# MCU063B_EtherCAT.net
KiCad netlist of a schematic drawn in Altium Designer
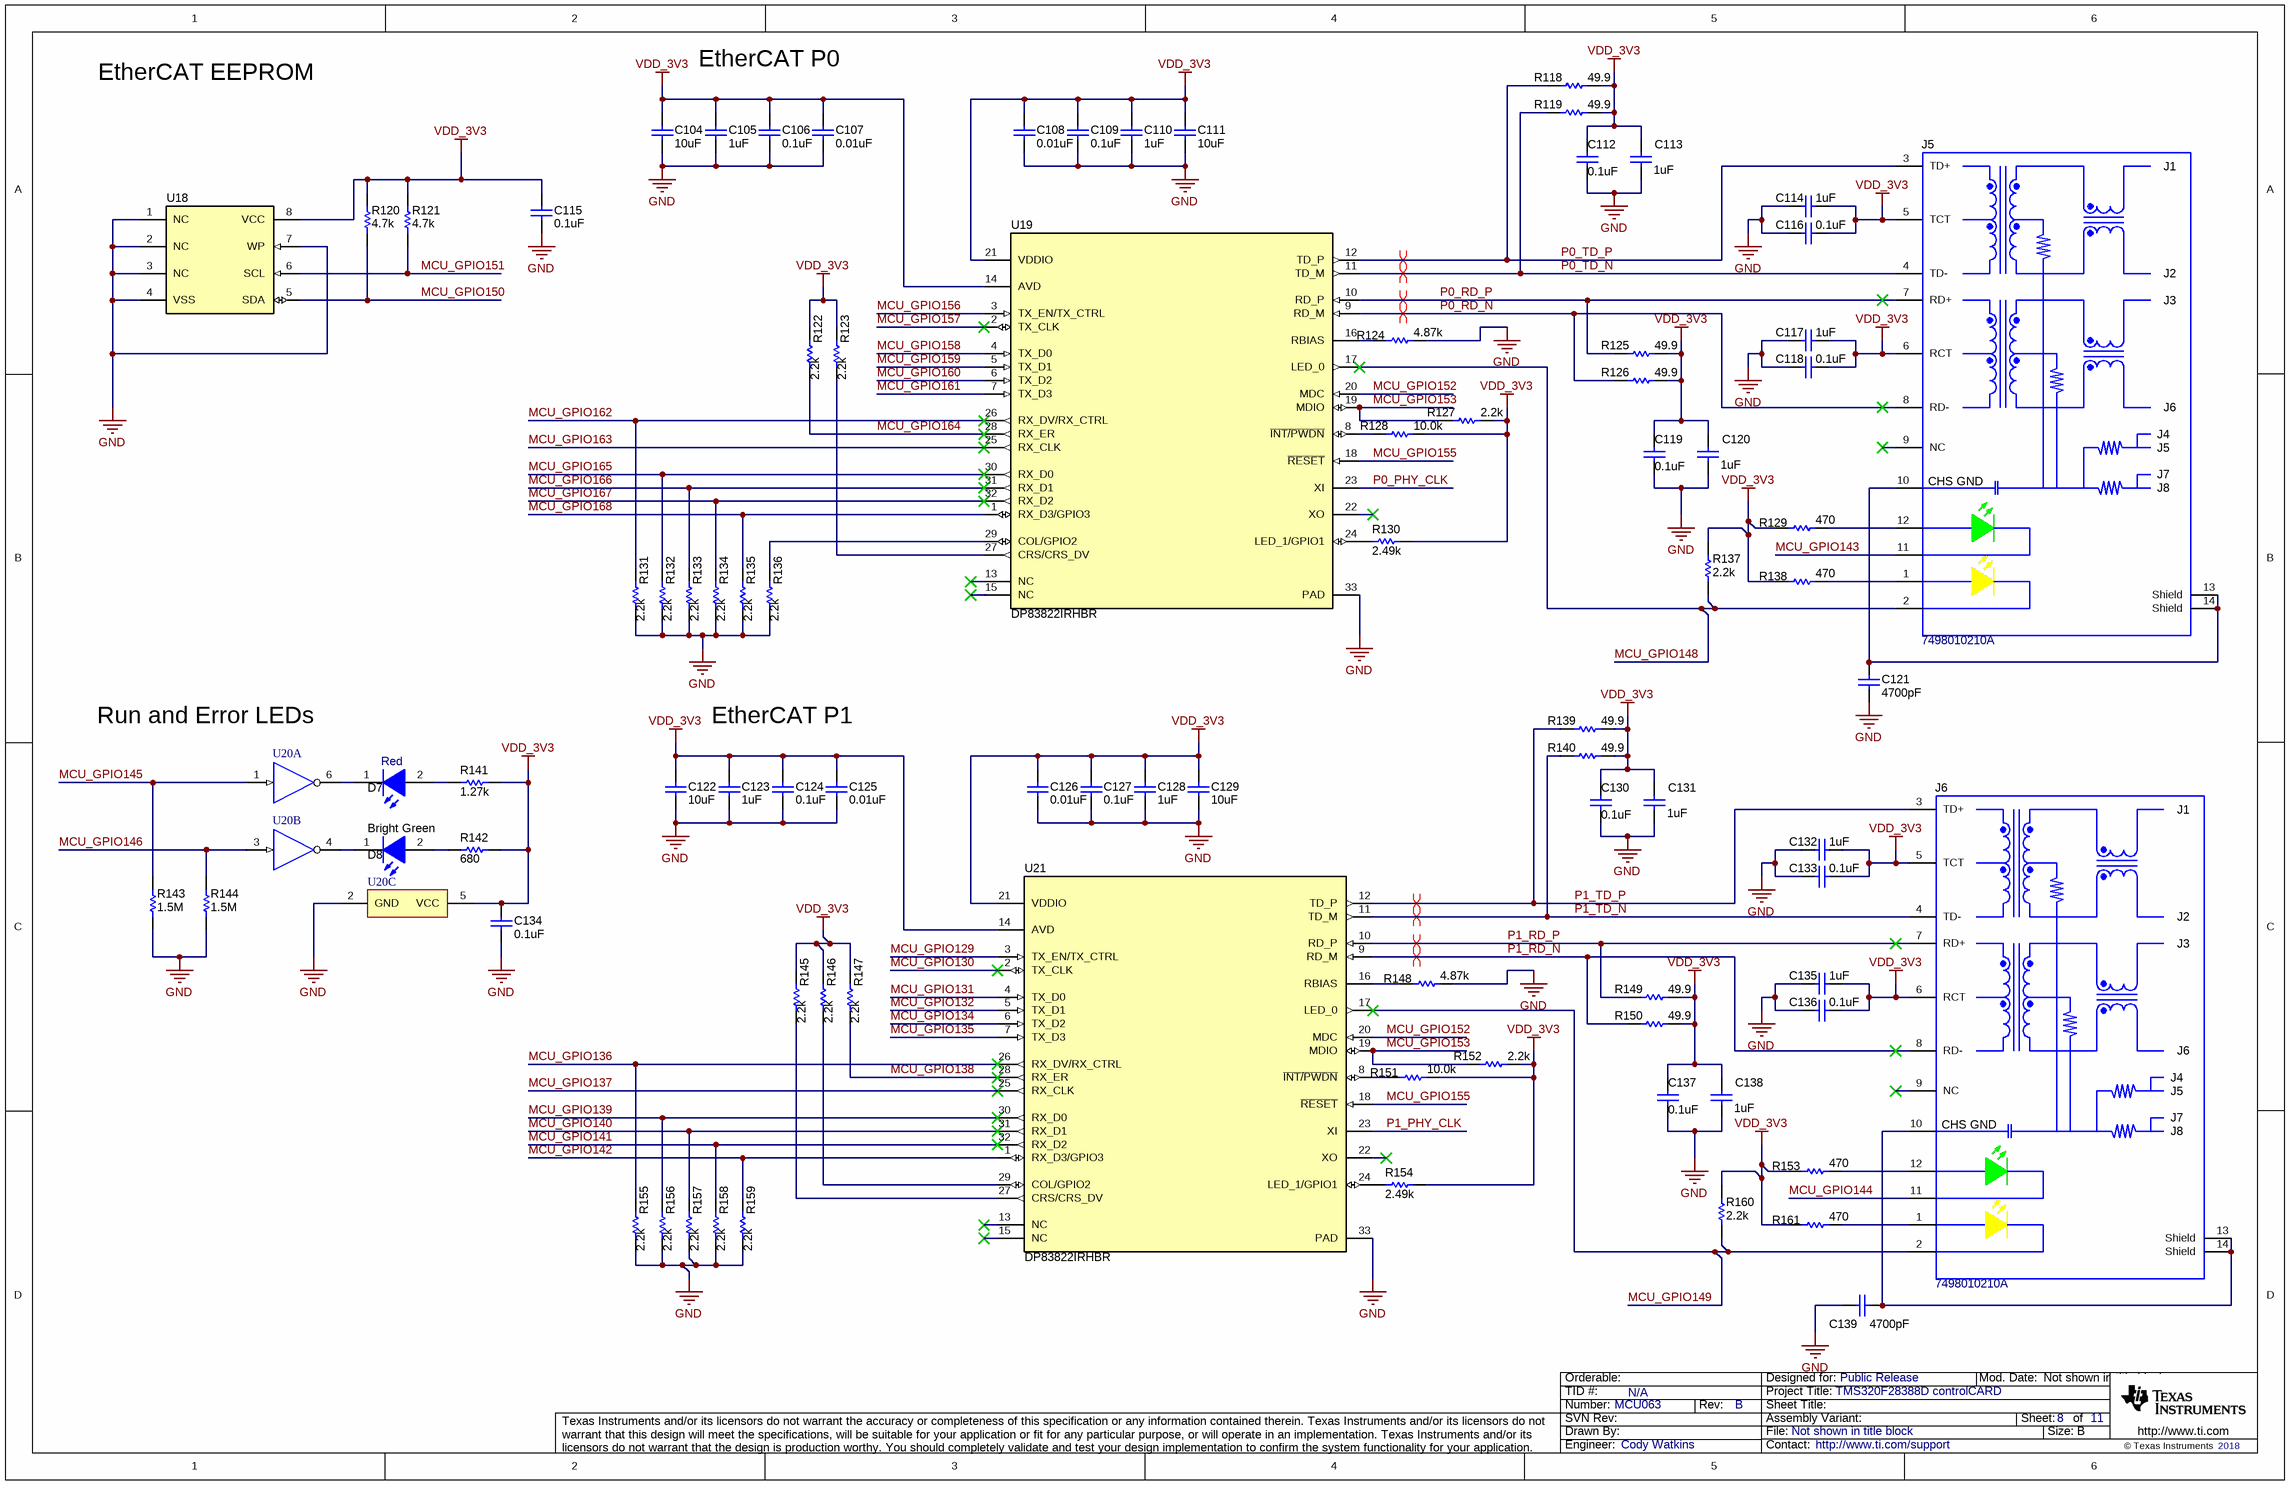
[diagram p0: MCU063B_EtherCAT.SchDoc]

(export (version "E")
  (design (tool "Eeschema 10.0.6"))
  (components
    (comp (ref "C104")
      (value "CL05A106MQ5NUNC")
      (footprint "0402")
      (description "CAP, CERM, 10 uF, 6.3 V, +/- 20%, X5R, 0402")
      (fields
        (field (name "MANUFACTURER") "Samsung Electro-Mechanics")
        (field (name "VALUEDISPLAYED") "10uF")
      )
      (libsource (lib "Altium Vault - TI") (part "Capacitor"))
    )
    (comp (ref "C105")
      (value "EMK105BJ105KVHF")
      (footprint "0402")
      (description "CAP, CERM, 1 uF, 16 V, +/- 10%, X5R, 0402")
      (fields (field (name "MANUFACTURER") "Taiyo Yuden") (field (name "VALUEDISPLAYED") "1uF"))
      (libsource (lib "Altium Vault - TI") (part "Capacitor"))
    )
    (comp (ref "C106")
      (value "LMK105BJ104KV-F")
      (footprint "0402")
      (description "CAP, CERM, 0.1 uF, 10 V,+/- 10%, X5R, 0402")
      (fields (field (name "MANUFACTURER") "Taiyo Yuden") (field (name "VALUEDISPLAYED") "0.1uF"))
      (libsource (lib "Altium Vault - TI") (part "Capacitor"))
    )
    (comp (ref "C107")
      (value "885012205031")
      (footprint "0402")
      (description "CAP, CERM, 0.01 uF, 16 V, +/- 10%, X7R, 0402")
      (fields (field (name "MANUFACTURER") "Wurth Elektronik") (field (name "VALUEDISPLAYED") "0.01uF"))
      (libsource (lib "Altium Vault - TI") (part "Capacitor"))
    )
    (comp (ref "C108")
      (value "885012205031")
      (footprint "0402")
      (description "CAP, CERM, 0.01 uF, 16 V, +/- 10%, X7R, 0402")
      (fields (field (name "MANUFACTURER") "Wurth Elektronik") (field (name "VALUEDISPLAYED") "0.01uF"))
      (libsource (lib "Altium Vault - TI") (part "Capacitor"))
    )
    (comp (ref "C109")
      (value "LMK105BJ104KV-F")
      (footprint "0402")
      (description "CAP, CERM, 0.1 uF, 10 V,+/- 10%, X5R, 0402")
      (fields (field (name "MANUFACTURER") "Taiyo Yuden") (field (name "VALUEDISPLAYED") "0.1uF"))
      (libsource (lib "Altium Vault - TI") (part "Capacitor"))
    )
    (comp (ref "C110")
      (value "EMK105BJ105KVHF")
      (footprint "0402")
      (description "CAP, CERM, 1 uF, 16 V, +/- 10%, X5R, 0402")
      (fields (field (name "MANUFACTURER") "Taiyo Yuden") (field (name "VALUEDISPLAYED") "1uF"))
      (libsource (lib "Altium Vault - TI") (part "Capacitor"))
    )
    (comp (ref "C111")
      (value "CL05A106MQ5NUNC")
      (footprint "0402")
      (description "CAP, CERM, 10 uF, 6.3 V, +/- 20%, X5R, 0402")
      (fields
        (field (name "MANUFACTURER") "Samsung Electro-Mechanics")
        (field (name "VALUEDISPLAYED") "10uF")
      )
      (libsource (lib "Altium Vault - TI") (part "Capacitor"))
    )
    (comp (ref "C112")
      (value "LMK105BJ104KV-F")
      (footprint "0402")
      (description "CAP, CERM, 0.1 uF, 10 V,+/- 10%, X5R, 0402")
      (fields (field (name "MANUFACTURER") "Taiyo Yuden") (field (name "VALUEDISPLAYED") "0.1uF"))
      (libsource (lib "Altium Vault - TI") (part "Capacitor"))
    )
    (comp (ref "C113")
      (value "EMK105BJ105KVHF")
      (footprint "0402")
      (description "CAP, CERM, 1 uF, 16 V, +/- 10%, X5R, 0402")
      (fields (field (name "MANUFACTURER") "Taiyo Yuden") (field (name "VALUEDISPLAYED") "1uF"))
      (libsource (lib "Altium Vault - TI") (part "Capacitor"))
    )
    (comp (ref "C114")
      (value "EMK105BJ105KVHF")
      (footprint "0402")
      (description "CAP, CERM, 1 uF, 16 V, +/- 10%, X5R, 0402")
      (fields (field (name "MANUFACTURER") "Taiyo Yuden") (field (name "VALUEDISPLAYED") "1uF"))
      (libsource (lib "Altium Vault - TI") (part "Capacitor"))
    )
    (comp (ref "C115")
      (value "CL05B104KP5NNNC")
      (footprint "0402")
      (description "CAP, CERM, 0.1 uF, 10 V, +/- 10%, X7R, 0402")
      (fields
        (field (name "VALUEDISPLAYED") "0.1uF")
        (field (name "MANUFACTURER") "Samsung Electro-Mechanics")
      )
      (libsource (lib "Altium Vault - TI") (part "Capacitor"))
    )
    (comp (ref "C116")
      (value "LMK105BJ104KV-F")
      (footprint "0402")
      (description "CAP, CERM, 0.1 uF, 10 V,+/- 10%, X5R, 0402")
      (fields (field (name "MANUFACTURER") "Taiyo Yuden") (field (name "VALUEDISPLAYED") "0.1uF"))
      (libsource (lib "Altium Vault - TI") (part "Capacitor"))
    )
    (comp (ref "C117")
      (value "EMK105BJ105KVHF")
      (footprint "0402")
      (description "CAP, CERM, 1 uF, 16 V, +/- 10%, X5R, 0402")
      (fields (field (name "MANUFACTURER") "Taiyo Yuden") (field (name "VALUEDISPLAYED") "1uF"))
      (libsource (lib "Altium Vault - TI") (part "Capacitor"))
    )
    (comp (ref "C118")
      (value "LMK105BJ104KV-F")
      (footprint "0402")
      (description "CAP, CERM, 0.1 uF, 10 V,+/- 10%, X5R, 0402")
      (fields (field (name "MANUFACTURER") "Taiyo Yuden") (field (name "VALUEDISPLAYED") "0.1uF"))
      (libsource (lib "Altium Vault - TI") (part "Capacitor"))
    )
    (comp (ref "C119")
      (value "LMK105BJ104KV-F")
      (footprint "0402")
      (description "CAP, CERM, 0.1 uF, 10 V,+/- 10%, X5R, 0402")
      (fields (field (name "MANUFACTURER") "Taiyo Yuden") (field (name "VALUEDISPLAYED") "0.1uF"))
      (libsource (lib "Altium Vault - TI") (part "Capacitor"))
    )
    (comp (ref "C120")
      (value "EMK105BJ105KVHF")
      (footprint "0402")
      (description "CAP, CERM, 1 uF, 16 V, +/- 10%, X5R, 0402")
      (fields (field (name "MANUFACTURER") "Taiyo Yuden") (field (name "VALUEDISPLAYED") "1uF"))
      (libsource (lib "Altium Vault - TI") (part "Capacitor"))
    )
    (comp (ref "C121")
      (value "12061C472KAT2A")
      (footprint "1206")
      (description "CAP, CERM, 4700 pF, 100 V, +/- 10%, X7R, 1206")
      (fields (field (name "MANUFACTURER") "AVX") (field (name "VALUEDISPLAYED") "4700pF"))
      (libsource (lib "Altium Vault - TI") (part "Capacitor"))
    )
    (comp (ref "C122")
      (value "CL05A106MQ5NUNC")
      (footprint "0402")
      (description "CAP, CERM, 10 uF, 6.3 V, +/- 20%, X5R, 0402")
      (fields
        (field (name "MANUFACTURER") "Samsung Electro-Mechanics")
        (field (name "VALUEDISPLAYED") "10uF")
      )
      (libsource (lib "Altium Vault - TI") (part "Capacitor"))
    )
    (comp (ref "C123")
      (value "EMK105BJ105KVHF")
      (footprint "0402")
      (description "CAP, CERM, 1 uF, 16 V, +/- 10%, X5R, 0402")
      (fields (field (name "MANUFACTURER") "Taiyo Yuden") (field (name "VALUEDISPLAYED") "1uF"))
      (libsource (lib "Altium Vault - TI") (part "Capacitor"))
    )
    (comp (ref "C124")
      (value "LMK105BJ104KV-F")
      (footprint "0402")
      (description "CAP, CERM, 0.1 uF, 10 V,+/- 10%, X5R, 0402")
      (fields (field (name "MANUFACTURER") "Taiyo Yuden") (field (name "VALUEDISPLAYED") "0.1uF"))
      (libsource (lib "Altium Vault - TI") (part "Capacitor"))
    )
    (comp (ref "C125")
      (value "885012205031")
      (footprint "0402")
      (description "CAP, CERM, 0.01 uF, 16 V, +/- 10%, X7R, 0402")
      (fields (field (name "MANUFACTURER") "Wurth Elektronik") (field (name "VALUEDISPLAYED") "0.01uF"))
      (libsource (lib "Altium Vault - TI") (part "Capacitor"))
    )
    (comp (ref "C126")
      (value "885012205031")
      (footprint "0402")
      (description "CAP, CERM, 0.01 uF, 16 V, +/- 10%, X7R, 0402")
      (fields (field (name "MANUFACTURER") "Wurth Elektronik") (field (name "VALUEDISPLAYED") "0.01uF"))
      (libsource (lib "Altium Vault - TI") (part "Capacitor"))
    )
    (comp (ref "C127")
      (value "LMK105BJ104KV-F")
      (footprint "0402")
      (description "CAP, CERM, 0.1 uF, 10 V,+/- 10%, X5R, 0402")
      (fields (field (name "MANUFACTURER") "Taiyo Yuden") (field (name "VALUEDISPLAYED") "0.1uF"))
      (libsource (lib "Altium Vault - TI") (part "Capacitor"))
    )
    (comp (ref "C128")
      (value "EMK105BJ105KVHF")
      (footprint "0402")
      (description "CAP, CERM, 1 uF, 16 V, +/- 10%, X5R, 0402")
      (fields (field (name "MANUFACTURER") "Taiyo Yuden") (field (name "VALUEDISPLAYED") "1uF"))
      (libsource (lib "Altium Vault - TI") (part "Capacitor"))
    )
    (comp (ref "C129")
      (value "CL05A106MQ5NUNC")
      (footprint "0402")
      (description "CAP, CERM, 10 uF, 6.3 V, +/- 20%, X5R, 0402")
      (fields
        (field (name "MANUFACTURER") "Samsung Electro-Mechanics")
        (field (name "VALUEDISPLAYED") "10uF")
      )
      (libsource (lib "Altium Vault - TI") (part "Capacitor"))
    )
    (comp (ref "C130")
      (value "LMK105BJ104KV-F")
      (footprint "0402")
      (description "CAP, CERM, 0.1 uF, 10 V,+/- 10%, X5R, 0402")
      (fields (field (name "MANUFACTURER") "Taiyo Yuden") (field (name "VALUEDISPLAYED") "0.1uF"))
      (libsource (lib "Altium Vault - TI") (part "Capacitor"))
    )
    (comp (ref "C131")
      (value "EMK105BJ105KVHF")
      (footprint "0402")
      (description "CAP, CERM, 1 uF, 16 V, +/- 10%, X5R, 0402")
      (fields (field (name "MANUFACTURER") "Taiyo Yuden") (field (name "VALUEDISPLAYED") "1uF"))
      (libsource (lib "Altium Vault - TI") (part "Capacitor"))
    )
    (comp (ref "C132")
      (value "EMK105BJ105KVHF")
      (footprint "0402")
      (description "CAP, CERM, 1 uF, 16 V, +/- 10%, X5R, 0402")
      (fields (field (name "MANUFACTURER") "Taiyo Yuden") (field (name "VALUEDISPLAYED") "1uF"))
      (libsource (lib "Altium Vault - TI") (part "Capacitor"))
    )
    (comp (ref "C133")
      (value "LMK105BJ104KV-F")
      (footprint "0402")
      (description "CAP, CERM, 0.1 uF, 10 V,+/- 10%, X5R, 0402")
      (fields (field (name "MANUFACTURER") "Taiyo Yuden") (field (name "VALUEDISPLAYED") "0.1uF"))
      (libsource (lib "Altium Vault - TI") (part "Capacitor"))
    )
    (comp (ref "C134")
      (value "CL05B104KP5NNNC")
      (footprint "0402")
      (description "CAP, CERM, 0.1 uF, 10 V, +/- 10%, X7R, 0402")
      (fields
        (field (name "VALUEDISPLAYED") "0.1uF")
        (field (name "MANUFACTURER") "Samsung Electro-Mechanics")
      )
      (libsource (lib "Altium Vault - TI") (part "Capacitor"))
    )
    (comp (ref "C135")
      (value "EMK105BJ105KVHF")
      (footprint "0402")
      (description "CAP, CERM, 1 uF, 16 V, +/- 10%, X5R, 0402")
      (fields (field (name "MANUFACTURER") "Taiyo Yuden") (field (name "VALUEDISPLAYED") "1uF"))
      (libsource (lib "Altium Vault - TI") (part "Capacitor"))
    )
    (comp (ref "C136")
      (value "LMK105BJ104KV-F")
      (footprint "0402")
      (description "CAP, CERM, 0.1 uF, 10 V,+/- 10%, X5R, 0402")
      (fields (field (name "MANUFACTURER") "Taiyo Yuden") (field (name "VALUEDISPLAYED") "0.1uF"))
      (libsource (lib "Altium Vault - TI") (part "Capacitor"))
    )
    (comp (ref "C137")
      (value "LMK105BJ104KV-F")
      (footprint "0402")
      (description "CAP, CERM, 0.1 uF, 10 V,+/- 10%, X5R, 0402")
      (fields (field (name "MANUFACTURER") "Taiyo Yuden") (field (name "VALUEDISPLAYED") "0.1uF"))
      (libsource (lib "Altium Vault - TI") (part "Capacitor"))
    )
    (comp (ref "C138")
      (value "EMK105BJ105KVHF")
      (footprint "0402")
      (description "CAP, CERM, 1 uF, 16 V, +/- 10%, X5R, 0402")
      (fields (field (name "MANUFACTURER") "Taiyo Yuden") (field (name "VALUEDISPLAYED") "1uF"))
      (libsource (lib "Altium Vault - TI") (part "Capacitor"))
    )
    (comp (ref "C139")
      (value "12061C472KAT2A")
      (footprint "1206")
      (description "CAP, CERM, 4700 pF, 100 V, +/- 10%, X7R, 1206")
      (fields (field (name "MANUFACTURER") "AVX") (field (name "VALUEDISPLAYED") "4700pF"))
      (libsource (lib "Altium Vault - TI") (part "Capacitor"))
    )
    (comp (ref "D7")
      (value "Red")
      (footprint "WL-SMCW_RED_0805")
      (description "LED, Red, SMD")
      (fields (field (name "PARTNUMBER") "150080SS75000") (field (name "MANUFACTURER") "Wurth Elektronik"))
      (libsource (lib "Altium Vault - TI") (part "LED_A2_K1"))
    )
    (comp (ref "D8")
      (value "Bright Green")
      (footprint "WL-SMCW_Green_0805")
      (description "LED, Bright Green, SMD")
      (fields (field (name "PARTNUMBER") "150080VS75000") (field (name "MANUFACTURER") "Wurth Elektronik"))
      (libsource (lib "Altium Vault - TI") (part "LED_A2_K1"))
    )
    (comp (ref "J5")
      (value "7498010210A")
      (footprint "Wurth_7498010210A")
      (description "Connector, RJ45, 1x1, Gold, R/A, SMT")
      (fields (field (name "MANUFACTURER") "Wurth Elektronik"))
      (libsource (lib "Altium Vault - TI") (part "Wurth_7498010210A"))
    )
    (comp (ref "J6")
      (value "7498010210A")
      (footprint "Wurth_7498010210A")
      (description "Connector, RJ45, 1x1, Gold, R/A, SMT")
      (fields (field (name "MANUFACTURER") "Wurth Elektronik"))
      (libsource (lib "Altium Vault - TI") (part "Wurth_7498010210A"))
    )
    (comp (ref "R118")
      (value "RC0402FR-0749R9L")
      (footprint "0402")
      (description "RES, 49.9, 1%, 0.063 W, 0402")
      (fields (field (name "MANUFACTURER") "Yageo America") (field (name "VALUEDISPLAYED") "49.9"))
      (libsource (lib "Altium Vault - TI") (part "Resistor"))
    )
    (comp (ref "R119")
      (value "RC0402FR-0749R9L")
      (footprint "0402")
      (description "RES, 49.9, 1%, 0.063 W, 0402")
      (fields (field (name "MANUFACTURER") "Yageo America") (field (name "VALUEDISPLAYED") "49.9"))
      (libsource (lib "Altium Vault - TI") (part "Resistor"))
    )
    (comp (ref "R120")
      (value "CRCW04024K70JNED")
      (footprint "0402")
      (description "RES, 4.7 k, 5%, 0.063 W, AEC-Q200 Grade 0, 0402")
      (fields (field (name "MANUFACTURER") "Vishay-Dale") (field (name "VALUEDISPLAYED") "4.7k"))
      (libsource (lib "Altium Vault - TI") (part "Resistor"))
    )
    (comp (ref "R121")
      (value "CRCW04024K70JNED")
      (footprint "0402")
      (description "RES, 4.7 k, 5%, 0.063 W, AEC-Q200 Grade 0, 0402")
      (fields (field (name "MANUFACTURER") "Vishay-Dale") (field (name "VALUEDISPLAYED") "4.7k"))
      (libsource (lib "Altium Vault - TI") (part "Resistor"))
    )
    (comp (ref "R122")
      (value "CRCW02012K20JNED")
      (footprint "0201")
      (description "RES, 2.2 k, 5%, 0.05 W, 0201")
      (fields (field (name "MANUFACTURER") "Vishay-Dale") (field (name "VALUEDISPLAYED") "2.2k"))
      (libsource (lib "Altium Vault - TI") (part "Resistor"))
    )
    (comp (ref "R123")
      (value "CRCW02012K20JNED")
      (footprint "0201")
      (description "RES, 2.2 k, 5%, 0.05 W, 0201")
      (fields (field (name "MANUFACTURER") "Vishay-Dale") (field (name "VALUEDISPLAYED") "2.2k"))
      (libsource (lib "Altium Vault - TI") (part "Resistor"))
    )
    (comp (ref "R124")
      (value "CRCW04024K87FKED")
      (footprint "0402")
      (description "RES, 4.87 k, 1%, 0.063 W, AEC-Q200 Grade 0, 0402")
      (fields (field (name "MANUFACTURER") "Vishay-Dale") (field (name "VALUEDISPLAYED") "4.87k"))
      (libsource (lib "Altium Vault - TI") (part "Resistor"))
    )
    (comp (ref "R125")
      (value "RC0402FR-0749R9L")
      (footprint "0402")
      (description "RES, 49.9, 1%, 0.063 W, 0402")
      (fields (field (name "MANUFACTURER") "Yageo America") (field (name "VALUEDISPLAYED") "49.9"))
      (libsource (lib "Altium Vault - TI") (part "Resistor"))
    )
    (comp (ref "R126")
      (value "RC0402FR-0749R9L")
      (footprint "0402")
      (description "RES, 49.9, 1%, 0.063 W, 0402")
      (fields (field (name "MANUFACTURER") "Yageo America") (field (name "VALUEDISPLAYED") "49.9"))
      (libsource (lib "Altium Vault - TI") (part "Resistor"))
    )
    (comp (ref "R127")
      (value "CRCW04022K20JNED")
      (footprint "0402")
      (description "RES, 2.2 k, 5%, 0.063 W, AEC-Q200 Grade 0, 0402")
      (fields (field (name "MANUFACTURER") "Vishay-Dale") (field (name "VALUEDISPLAYED") "2.2k"))
      (libsource (lib "Altium Vault - TI") (part "Resistor"))
    )
    (comp (ref "R128")
      (value "RC0402FR-0710KL")
      (footprint "0402")
      (description "RES, 10.0 k, 1%, 0.063 W, 0402")
      (fields (field (name "MANUFACTURER") "Yageo America") (field (name "VALUEDISPLAYED") "10.0k"))
      (libsource (lib "Altium Vault - TI") (part "Resistor"))
    )
    (comp (ref "R129")
      (value "CRCW0603470RJNEA")
      (footprint "0603")
      (description "RES, 470, 5%, 0.1 W, AEC-Q200 Grade 0, 0603")
      (fields (field (name "MANUFACTURER") "Vishay-Dale") (field (name "VALUEDISPLAYED") "470"))
      (libsource (lib "Altium Vault - TI") (part "Resistor"))
    )
    (comp (ref "R130")
      (value "CRCW04022K49FKED")
      (footprint "0402")
      (description "RES, 2.49 k, 1%, 0.063 W, AEC-Q200 Grade 0, 0402")
      (fields (field (name "MANUFACTURER") "Vishay-Dale") (field (name "VALUEDISPLAYED") "2.49k"))
      (libsource (lib "Altium Vault - TI") (part "Resistor"))
    )
    (comp (ref "R131")
      (value "CRCW02012K20JNED")
      (footprint "0201")
      (description "RES, 2.2 k, 5%, 0.05 W, 0201")
      (fields (field (name "MANUFACTURER") "Vishay-Dale") (field (name "VALUEDISPLAYED") "2.2k"))
      (libsource (lib "Altium Vault - TI") (part "Resistor"))
    )
    (comp (ref "R132")
      (value "CRCW02012K20JNED")
      (footprint "0201")
      (description "RES, 2.2 k, 5%, 0.05 W, 0201")
      (fields (field (name "MANUFACTURER") "Vishay-Dale") (field (name "VALUEDISPLAYED") "2.2k"))
      (libsource (lib "Altium Vault - TI") (part "Resistor"))
    )
    (comp (ref "R133")
      (value "CRCW02012K20JNED")
      (footprint "0201")
      (description "RES, 2.2 k, 5%, 0.05 W, 0201")
      (fields (field (name "MANUFACTURER") "Vishay-Dale") (field (name "VALUEDISPLAYED") "2.2k"))
      (libsource (lib "Altium Vault - TI") (part "Resistor"))
    )
    (comp (ref "R134")
      (value "CRCW02012K20JNED")
      (footprint "0201")
      (description "RES, 2.2 k, 5%, 0.05 W, 0201")
      (fields (field (name "MANUFACTURER") "Vishay-Dale") (field (name "VALUEDISPLAYED") "2.2k"))
      (libsource (lib "Altium Vault - TI") (part "Resistor"))
    )
    (comp (ref "R135")
      (value "CRCW02012K20JNED")
      (footprint "0201")
      (description "RES, 2.2 k, 5%, 0.05 W, 0201")
      (fields (field (name "MANUFACTURER") "Vishay-Dale") (field (name "VALUEDISPLAYED") "2.2k"))
      (libsource (lib "Altium Vault - TI") (part "Resistor"))
    )
    (comp (ref "R136")
      (value "CRCW02012K20JNED")
      (footprint "0201")
      (description "RES, 2.2 k, 5%, 0.05 W, 0201")
      (fields (field (name "MANUFACTURER") "Vishay-Dale") (field (name "VALUEDISPLAYED") "2.2k"))
      (libsource (lib "Altium Vault - TI") (part "Resistor"))
    )
    (comp (ref "R137")
      (value "CRCW04022K20JNED")
      (footprint "0402")
      (description "RES, 2.2 k, 5%, 0.063 W, AEC-Q200 Grade 0, 0402")
      (fields (field (name "MANUFACTURER") "Vishay-Dale") (field (name "VALUEDISPLAYED") "2.2k"))
      (libsource (lib "Altium Vault - TI") (part "Resistor"))
    )
    (comp (ref "R138")
      (value "CRCW0603470RJNEA")
      (footprint "0603")
      (description "RES, 470, 5%, 0.1 W, AEC-Q200 Grade 0, 0603")
      (fields (field (name "MANUFACTURER") "Vishay-Dale") (field (name "VALUEDISPLAYED") "470"))
      (libsource (lib "Altium Vault - TI") (part "Resistor"))
    )
    (comp (ref "R139")
      (value "RC0402FR-0749R9L")
      (footprint "0402")
      (description "RES, 49.9, 1%, 0.063 W, 0402")
      (fields (field (name "MANUFACTURER") "Yageo America") (field (name "VALUEDISPLAYED") "49.9"))
      (libsource (lib "Altium Vault - TI") (part "Resistor"))
    )
    (comp (ref "R140")
      (value "RC0402FR-0749R9L")
      (footprint "0402")
      (description "RES, 49.9, 1%, 0.063 W, 0402")
      (fields (field (name "MANUFACTURER") "Yageo America") (field (name "VALUEDISPLAYED") "49.9"))
      (libsource (lib "Altium Vault - TI") (part "Resistor"))
    )
    (comp (ref "R141")
      (value "CRCW04021K27FKED")
      (footprint "0402")
      (description "RES, 1.27 k, 1%, 0.063 W, AEC-Q200 Grade 0, 0402")
      (fields (field (name "MANUFACTURER") "Vishay-Dale") (field (name "VALUEDISPLAYED") "1.27k"))
      (libsource (lib "Altium Vault - TI") (part "Resistor"))
    )
    (comp (ref "R142")
      (value "CRCW0402680RJNED")
      (footprint "0402")
      (description "RES, 680, 5%, 0.063 W, AEC-Q200 Grade 0, 0402")
      (fields (field (name "VALUEDISPLAYED") "680") (field (name "MANUFACTURER") "Vishay-Dale"))
      (libsource (lib "Altium Vault - TI") (part "Resistor"))
    )
    (comp (ref "R143")
      (value "CRCW04021M50JNED")
      (footprint "0402")
      (description "RES, 1.5 M, 5%, 0.063 W, AEC-Q200 Grade 0, 0402")
      (fields (field (name "MANUFACTURER") "Vishay-Dale") (field (name "VALUEDISPLAYED") "1.5M"))
      (libsource (lib "Altium Vault - TI") (part "Resistor"))
    )
    (comp (ref "R144")
      (value "CRCW04021M50JNED")
      (footprint "0402")
      (description "RES, 1.5 M, 5%, 0.063 W, AEC-Q200 Grade 0, 0402")
      (fields (field (name "MANUFACTURER") "Vishay-Dale") (field (name "VALUEDISPLAYED") "1.5M"))
      (libsource (lib "Altium Vault - TI") (part "Resistor"))
    )
    (comp (ref "R145")
      (value "CRCW02012K20JNED")
      (footprint "0201")
      (description "RES, 2.2 k, 5%, 0.05 W, 0201")
      (fields (field (name "MANUFACTURER") "Vishay-Dale") (field (name "VALUEDISPLAYED") "2.2k"))
      (libsource (lib "Altium Vault - TI") (part "Resistor"))
    )
    (comp (ref "R146")
      (value "CRCW02012K20JNED")
      (footprint "0201")
      (description "RES, 2.2 k, 5%, 0.05 W, 0201")
      (fields (field (name "MANUFACTURER") "Vishay-Dale") (field (name "VALUEDISPLAYED") "2.2k"))
      (libsource (lib "Altium Vault - TI") (part "Resistor"))
    )
    (comp (ref "R147")
      (value "CRCW02012K20JNED")
      (footprint "0201")
      (description "RES, 2.2 k, 5%, 0.05 W, 0201")
      (fields (field (name "MANUFACTURER") "Vishay-Dale") (field (name "VALUEDISPLAYED") "2.2k"))
      (libsource (lib "Altium Vault - TI") (part "Resistor"))
    )
    (comp (ref "R148")
      (value "CRCW04024K87FKED")
      (footprint "0402")
      (description "RES, 4.87 k, 1%, 0.063 W, AEC-Q200 Grade 0, 0402")
      (fields (field (name "MANUFACTURER") "Vishay-Dale") (field (name "VALUEDISPLAYED") "4.87k"))
      (libsource (lib "Altium Vault - TI") (part "Resistor"))
    )
    (comp (ref "R149")
      (value "RC0402FR-0749R9L")
      (footprint "0402")
      (description "RES, 49.9, 1%, 0.063 W, 0402")
      (fields (field (name "MANUFACTURER") "Yageo America") (field (name "VALUEDISPLAYED") "49.9"))
      (libsource (lib "Altium Vault - TI") (part "Resistor"))
    )
    (comp (ref "R150")
      (value "RC0402FR-0749R9L")
      (footprint "0402")
      (description "RES, 49.9, 1%, 0.063 W, 0402")
      (fields (field (name "MANUFACTURER") "Yageo America") (field (name "VALUEDISPLAYED") "49.9"))
      (libsource (lib "Altium Vault - TI") (part "Resistor"))
    )
    (comp (ref "R151")
      (value "RC0402FR-0710KL")
      (footprint "0402")
      (description "RES, 10.0 k, 1%, 0.063 W, 0402")
      (fields (field (name "MANUFACTURER") "Yageo America") (field (name "VALUEDISPLAYED") "10.0k"))
      (libsource (lib "Altium Vault - TI") (part "Resistor"))
    )
    (comp (ref "R152")
      (value "CRCW04022K20JNED")
      (footprint "0402")
      (description "RES, 2.2 k, 5%, 0.063 W, AEC-Q200 Grade 0, 0402")
      (fields (field (name "MANUFACTURER") "Vishay-Dale") (field (name "VALUEDISPLAYED") "2.2k"))
      (libsource (lib "Altium Vault - TI") (part "Resistor"))
    )
    (comp (ref "R153")
      (value "CRCW0603470RJNEA")
      (footprint "0603")
      (description "RES, 470, 5%, 0.1 W, AEC-Q200 Grade 0, 0603")
      (fields (field (name "MANUFACTURER") "Vishay-Dale") (field (name "VALUEDISPLAYED") "470"))
      (libsource (lib "Altium Vault - TI") (part "Resistor"))
    )
    (comp (ref "R154")
      (value "CRCW04022K49FKED")
      (footprint "0402")
      (description "RES, 2.49 k, 1%, 0.063 W, AEC-Q200 Grade 0, 0402")
      (fields (field (name "MANUFACTURER") "Vishay-Dale") (field (name "VALUEDISPLAYED") "2.49k"))
      (libsource (lib "Altium Vault - TI") (part "Resistor"))
    )
    (comp (ref "R155")
      (value "CRCW02012K20JNED")
      (footprint "0201")
      (description "RES, 2.2 k, 5%, 0.05 W, 0201")
      (fields (field (name "MANUFACTURER") "Vishay-Dale") (field (name "VALUEDISPLAYED") "2.2k"))
      (libsource (lib "Altium Vault - TI") (part "Resistor"))
    )
    (comp (ref "R156")
      (value "CRCW02012K20JNED")
      (footprint "0201")
      (description "RES, 2.2 k, 5%, 0.05 W, 0201")
      (fields (field (name "MANUFACTURER") "Vishay-Dale") (field (name "VALUEDISPLAYED") "2.2k"))
      (libsource (lib "Altium Vault - TI") (part "Resistor"))
    )
    (comp (ref "R157")
      (value "CRCW02012K20JNED")
      (footprint "0201")
      (description "RES, 2.2 k, 5%, 0.05 W, 0201")
      (fields (field (name "MANUFACTURER") "Vishay-Dale") (field (name "VALUEDISPLAYED") "2.2k"))
      (libsource (lib "Altium Vault - TI") (part "Resistor"))
    )
    (comp (ref "R158")
      (value "CRCW02012K20JNED")
      (footprint "0201")
      (description "RES, 2.2 k, 5%, 0.05 W, 0201")
      (fields (field (name "MANUFACTURER") "Vishay-Dale") (field (name "VALUEDISPLAYED") "2.2k"))
      (libsource (lib "Altium Vault - TI") (part "Resistor"))
    )
    (comp (ref "R159")
      (value "CRCW02012K20JNED")
      (footprint "0201")
      (description "RES, 2.2 k, 5%, 0.05 W, 0201")
      (fields (field (name "MANUFACTURER") "Vishay-Dale") (field (name "VALUEDISPLAYED") "2.2k"))
      (libsource (lib "Altium Vault - TI") (part "Resistor"))
    )
    (comp (ref "R160")
      (value "CRCW04022K20JNED")
      (footprint "0402")
      (description "RES, 2.2 k, 5%, 0.063 W, AEC-Q200 Grade 0, 0402")
      (fields (field (name "MANUFACTURER") "Vishay-Dale") (field (name "VALUEDISPLAYED") "2.2k"))
      (libsource (lib "Altium Vault - TI") (part "Resistor"))
    )
    (comp (ref "R161")
      (value "CRCW0603470RJNEA")
      (footprint "0603")
      (description "RES, 470, 5%, 0.1 W, AEC-Q200 Grade 0, 0603")
      (fields (field (name "MANUFACTURER") "Vishay-Dale") (field (name "VALUEDISPLAYED") "470"))
      (libsource (lib "Altium Vault - TI") (part "Resistor"))
    )
    (comp (ref "U18")
      (value "CAT24C16WI-GT3")
      (footprint "SOIC-8")
      (description "16 Kb I2C EEPROM Serial, SOIC-8")
      (fields (field (name "MANUFACTURER") "ON Semiconductor"))
      (libsource (lib "Altium Vault - TI") (part "EEPROM_8P_1-3NC"))
    )
    (comp (ref "U19")
      (value "DP83822IRHBR")
      (footprint "RHB0032B")
      (description "Robust, Low Power 10/100 Ethernet Physical Layer Transceiver, RHB0032B (VQFN-32)")
      (fields
        (field (name "ALTERNATE PARTNUMBER") "DP83822IRHBT")
        (field (name "PARTNUMBER") "DP83822IRHBR")
        (field (name "MANUFACTURER") "Texas Instruments")
      )
      (libsource (lib "Altium Vault - TI") (part "DP83822"))
    )
    (comp (ref "U20")
      (value "SN74LVC2G06DBVR")
      (footprint "DBV0006A_N")
      (description "Dual Inverter Buffer/Driver with Open-Drain Output, DBV0006A, LARGE T&R")
      (fields
        (field (name "MANUFACTURER") "Texas Instruments")
        (field (name "GENERIC PART NUMBER") "SN74LVC2G06")
      )
      (libsource (lib "Altium Vault - TI") (part "TI-SN74XXX2G06-XX-6"))
    )
    (comp (ref "U21")
      (value "DP83822IRHBR")
      (footprint "RHB0032B")
      (description "Robust, Low Power 10/100 Ethernet Physical Layer Transceiver, RHB0032B (VQFN-32)")
      (fields
        (field (name "ALTERNATE PARTNUMBER") "DP83822IRHBT")
        (field (name "PARTNUMBER") "DP83822IRHBR")
        (field (name "MANUFACTURER") "Texas Instruments")
      )
      (libsource (lib "Altium Vault - TI") (part "DP83822"))
    )
  )
  (nets
    (net (code "1") (name "/MCU_GPIO129") (class "Default")
      (node (ref "U21") (pin "3") (pinfunction "TX_EN/TX_CTRL_3") (pintype "input"))
    )
    (net (code "2") (name "/MCU_GPIO130") (class "Default")
      (node (ref "U21") (pin "2") (pinfunction "TX_CLK_2") (pintype "bidirectional+no_connect"))
    )
    (net (code "3") (name "/MCU_GPIO131") (class "Default")
      (node (ref "U21") (pin "4") (pinfunction "TX_D0_4") (pintype "input"))
    )
    (net (code "4") (name "/MCU_GPIO132") (class "Default")
      (node (ref "U21") (pin "5") (pinfunction "TX_D1_5") (pintype "input"))
    )
    (net (code "5") (name "/MCU_GPIO134") (class "Default")
      (node (ref "U21") (pin "6") (pinfunction "TX_D2_6") (pintype "input"))
    )
    (net (code "6") (name "/MCU_GPIO135") (class "Default")
      (node (ref "U21") (pin "7") (pinfunction "TX_D3_7") (pintype "input"))
    )
    (net (code "7") (name "/MCU_GPIO136") (class "Default")
      (node (ref "R155") (pin "2") (pinfunction "2_2") (pintype "passive"))
      (node (ref "U21") (pin "26") (pinfunction "RX_DV/RX_CTRL_26") (pintype "output"))
    )
    (net (code "8") (name "/MCU_GPIO137") (class "Default")
      (node (ref "U21") (pin "25") (pinfunction "RX_CLK_25") (pintype "output+no_connect"))
    )
    (net (code "9") (name "/MCU_GPIO138") (class "Default")
      (node (ref "R147") (pin "1") (pinfunction "1_1") (pintype "passive"))
      (node (ref "U21") (pin "28") (pinfunction "RX_ER_28") (pintype "output"))
    )
    (net (code "10") (name "/MCU_GPIO139") (class "Default")
      (node (ref "R156") (pin "2") (pinfunction "2_2") (pintype "passive"))
      (node (ref "U21") (pin "30") (pinfunction "RX_D0_30") (pintype "output"))
    )
    (net (code "11") (name "/MCU_GPIO140") (class "Default")
      (node (ref "R157") (pin "2") (pinfunction "2_2") (pintype "passive"))
      (node (ref "U21") (pin "31") (pinfunction "RX_D1_31") (pintype "output"))
    )
    (net (code "12") (name "/MCU_GPIO141") (class "Default")
      (node (ref "R158") (pin "2") (pinfunction "2_2") (pintype "passive"))
      (node (ref "U21") (pin "32") (pinfunction "RX_D2_32") (pintype "output"))
    )
    (net (code "13") (name "/MCU_GPIO142") (class "Default")
      (node (ref "R159") (pin "2") (pinfunction "2_2") (pintype "passive"))
      (node (ref "U21") (pin "1") (pinfunction "RX_D3/GPIO3_1") (pintype "bidirectional"))
    )
    (net (code "14") (name "/MCU_GPIO143") (class "Default")
      (node (ref "J5") (pin "11") (pinfunction "LEFT_LED_CATHODE_11") (pintype "passive"))
    )
    (net (code "15") (name "/MCU_GPIO144") (class "Default")
      (node (ref "J6") (pin "11") (pinfunction "LEFT_LED_CATHODE_11") (pintype "passive"))
    )
    (net (code "16") (name "/MCU_GPIO145") (class "Default")
      (node (ref "R143") (pin "1") (pinfunction "1_1") (pintype "passive"))
      (node (ref "U20") (pin "1") (pinfunction "1A_1") (pintype "input"))
    )
    (net (code "17") (name "/MCU_GPIO146") (class "Default")
      (node (ref "R144") (pin "1") (pinfunction "1_1") (pintype "passive"))
      (node (ref "U20") (pin "3") (pinfunction "2A_3") (pintype "input"))
    )
    (net (code "18") (name "/MCU_GPIO148") (class "Default")
      (node (ref "J5") (pin "2") (pinfunction "RIGHT_LED_CATHODE_2") (pintype "passive"))
      (node (ref "R137") (pin "1") (pinfunction "1_1") (pintype "passive"))
      (node (ref "U19") (pin "17") (pinfunction "LED_0_17") (pintype "output"))
    )
    (net (code "19") (name "/MCU_GPIO149") (class "Default")
      (node (ref "J6") (pin "2") (pinfunction "RIGHT_LED_CATHODE_2") (pintype "passive"))
      (node (ref "R160") (pin "1") (pinfunction "1_1") (pintype "passive"))
      (node (ref "U21") (pin "17") (pinfunction "LED_0_17") (pintype "output"))
    )
    (net (code "20") (name "/MCU_GPIO150") (class "Default")
      (node (ref "R120") (pin "1") (pinfunction "1_1") (pintype "passive"))
      (node (ref "U18") (pin "5") (pinfunction "SDA_5") (pintype "bidirectional"))
    )
    (net (code "21") (name "/MCU_GPIO151") (class "Default")
      (node (ref "R121") (pin "1") (pinfunction "1_1") (pintype "passive"))
      (node (ref "U18") (pin "6") (pinfunction "SCL_6") (pintype "input"))
    )
    (net (code "22") (name "/MCU_GPIO152") (class "Default")
      (node (ref "U19") (pin "20") (pinfunction "MDC_20") (pintype "input"))
      (node (ref "U21") (pin "20") (pinfunction "MDC_20") (pintype "input"))
    )
    (net (code "23") (name "/MCU_GPIO153") (class "Default")
      (node (ref "R127") (pin "2") (pinfunction "2_2") (pintype "passive"))
      (node (ref "R152") (pin "2") (pinfunction "2_2") (pintype "passive"))
      (node (ref "U19") (pin "19") (pinfunction "MDIO_19") (pintype "bidirectional"))
      (node (ref "U21") (pin "19") (pinfunction "MDIO_19") (pintype "bidirectional"))
    )
    (net (code "24") (name "/MCU_GPIO155") (class "Default")
      (node (ref "U19") (pin "18") (pinfunction "RESET_18") (pintype "input"))
      (node (ref "U21") (pin "18") (pinfunction "RESET_18") (pintype "input"))
    )
    (net (code "25") (name "/MCU_GPIO156") (class "Default")
      (node (ref "U19") (pin "3") (pinfunction "TX_EN/TX_CTRL_3") (pintype "input"))
    )
    (net (code "26") (name "/MCU_GPIO157") (class "Default")
      (node (ref "U19") (pin "2") (pinfunction "TX_CLK_2") (pintype "bidirectional+no_connect"))
    )
    (net (code "27") (name "/MCU_GPIO158") (class "Default")
      (node (ref "U19") (pin "4") (pinfunction "TX_D0_4") (pintype "input"))
    )
    (net (code "28") (name "/MCU_GPIO159") (class "Default")
      (node (ref "U19") (pin "5") (pinfunction "TX_D1_5") (pintype "input"))
    )
    (net (code "29") (name "/MCU_GPIO160") (class "Default")
      (node (ref "U19") (pin "6") (pinfunction "TX_D2_6") (pintype "input"))
    )
    (net (code "30") (name "/MCU_GPIO161") (class "Default")
      (node (ref "U19") (pin "7") (pinfunction "TX_D3_7") (pintype "input"))
    )
    (net (code "31") (name "/MCU_GPIO162") (class "Default")
      (node (ref "R131") (pin "2") (pinfunction "2_2") (pintype "passive"))
      (node (ref "U19") (pin "26") (pinfunction "RX_DV/RX_CTRL_26") (pintype "output"))
    )
    (net (code "32") (name "/MCU_GPIO163") (class "Default")
      (node (ref "U19") (pin "25") (pinfunction "RX_CLK_25") (pintype "output+no_connect"))
    )
    (net (code "33") (name "/MCU_GPIO164") (class "Default")
      (node (ref "R122") (pin "1") (pinfunction "1_1") (pintype "passive"))
      (node (ref "U19") (pin "28") (pinfunction "RX_ER_28") (pintype "output"))
    )
    (net (code "34") (name "/MCU_GPIO165") (class "Default")
      (node (ref "R132") (pin "2") (pinfunction "2_2") (pintype "passive"))
      (node (ref "U19") (pin "30") (pinfunction "RX_D0_30") (pintype "output"))
    )
    (net (code "35") (name "/MCU_GPIO166") (class "Default")
      (node (ref "R133") (pin "2") (pinfunction "2_2") (pintype "passive"))
      (node (ref "U19") (pin "31") (pinfunction "RX_D1_31") (pintype "output"))
    )
    (net (code "36") (name "/MCU_GPIO167") (class "Default")
      (node (ref "R134") (pin "2") (pinfunction "2_2") (pintype "passive"))
      (node (ref "U19") (pin "32") (pinfunction "RX_D2_32") (pintype "output"))
    )
    (net (code "37") (name "/MCU_GPIO168") (class "Default")
      (node (ref "R135") (pin "2") (pinfunction "2_2") (pintype "passive"))
      (node (ref "U19") (pin "1") (pinfunction "RX_D3/GPIO3_1") (pintype "bidirectional"))
    )
    (net (code "38") (name "/P0_PHY_CLK") (class "Default")
      (node (ref "U19") (pin "23") (pinfunction "XI_23") (pintype "passive"))
    )
    (net (code "39") (name "/P0_RD_N") (class "Default")
      (node (ref "J5") (pin "8") (pinfunction "RD-_8") (pintype "passive"))
      (node (ref "R126") (pin "1") (pinfunction "1_1") (pintype "passive"))
      (node (ref "U19") (pin "9") (pinfunction "RD_M_9") (pintype "input"))
    )
    (net (code "40") (name "/P0_RD_P") (class "Default")
      (node (ref "J5") (pin "7") (pinfunction "RD+_7") (pintype "passive"))
      (node (ref "R125") (pin "1") (pinfunction "1_1") (pintype "passive"))
      (node (ref "U19") (pin "10") (pinfunction "RD_P_10") (pintype "input"))
    )
    (net (code "41") (name "/P0_TD_N") (class "Default")
      (node (ref "J5") (pin "4") (pinfunction "TD-_4") (pintype "passive"))
      (node (ref "R119") (pin "1") (pinfunction "1_1") (pintype "passive"))
      (node (ref "U19") (pin "11") (pinfunction "TD_M_11") (pintype "output"))
    )
    (net (code "42") (name "/P0_TD_P") (class "Default")
      (node (ref "J5") (pin "3") (pinfunction "TD+_3") (pintype "passive"))
      (node (ref "R118") (pin "1") (pinfunction "1_1") (pintype "passive"))
      (node (ref "U19") (pin "12") (pinfunction "TD_P_12") (pintype "output"))
    )
    (net (code "43") (name "/P1_PHY_CLK") (class "Default")
      (node (ref "U21") (pin "23") (pinfunction "XI_23") (pintype "passive"))
    )
    (net (code "44") (name "/P1_RD_N") (class "Default")
      (node (ref "J6") (pin "8") (pinfunction "RD-_8") (pintype "passive"))
      (node (ref "R150") (pin "1") (pinfunction "1_1") (pintype "passive"))
      (node (ref "U21") (pin "9") (pinfunction "RD_M_9") (pintype "input"))
    )
    (net (code "45") (name "/P1_RD_P") (class "Default")
      (node (ref "J6") (pin "7") (pinfunction "RD+_7") (pintype "passive"))
      (node (ref "R149") (pin "1") (pinfunction "1_1") (pintype "passive"))
      (node (ref "U21") (pin "10") (pinfunction "RD_P_10") (pintype "input"))
    )
    (net (code "46") (name "/P1_TD_N") (class "Default")
      (node (ref "J6") (pin "4") (pinfunction "TD-_4") (pintype "passive"))
      (node (ref "R140") (pin "1") (pinfunction "1_1") (pintype "passive"))
      (node (ref "U21") (pin "11") (pinfunction "TD_M_11") (pintype "output"))
    )
    (net (code "47") (name "/P1_TD_P") (class "Default")
      (node (ref "J6") (pin "3") (pinfunction "TD+_3") (pintype "passive"))
      (node (ref "R139") (pin "1") (pinfunction "1_1") (pintype "passive"))
      (node (ref "U21") (pin "12") (pinfunction "TD_P_12") (pintype "output"))
    )
    (net (code "48") (name "GND") (class "Default")
      (node (ref "C104") (pin "2") (pinfunction "2_2") (pintype "passive"))
      (node (ref "C105") (pin "2") (pinfunction "2_2") (pintype "passive"))
      (node (ref "C106") (pin "2") (pinfunction "2_2") (pintype "passive"))
      (node (ref "C107") (pin "2") (pinfunction "2_2") (pintype "passive"))
      (node (ref "C108") (pin "2") (pinfunction "2_2") (pintype "passive"))
      (node (ref "C109") (pin "2") (pinfunction "2_2") (pintype "passive"))
      (node (ref "C110") (pin "2") (pinfunction "2_2") (pintype "passive"))
      (node (ref "C111") (pin "2") (pinfunction "2_2") (pintype "passive"))
      (node (ref "C112") (pin "2") (pinfunction "2_2") (pintype "passive"))
      (node (ref "C113") (pin "2") (pinfunction "2_2") (pintype "passive"))
      (node (ref "C114") (pin "1") (pinfunction "1_1") (pintype "passive"))
      (node (ref "C115") (pin "2") (pinfunction "2_2") (pintype "passive"))
      (node (ref "C116") (pin "1") (pinfunction "1_1") (pintype "passive"))
      (node (ref "C117") (pin "1") (pinfunction "1_1") (pintype "passive"))
      (node (ref "C118") (pin "1") (pinfunction "1_1") (pintype "passive"))
      (node (ref "C119") (pin "2") (pinfunction "2_2") (pintype "passive"))
      (node (ref "C120") (pin "2") (pinfunction "2_2") (pintype "passive"))
      (node (ref "C121") (pin "1") (pinfunction "1_1") (pintype "passive"))
      (node (ref "C122") (pin "2") (pinfunction "2_2") (pintype "passive"))
      (node (ref "C123") (pin "2") (pinfunction "2_2") (pintype "passive"))
      (node (ref "C124") (pin "2") (pinfunction "2_2") (pintype "passive"))
      (node (ref "C125") (pin "2") (pinfunction "2_2") (pintype "passive"))
      (node (ref "C126") (pin "2") (pinfunction "2_2") (pintype "passive"))
      (node (ref "C127") (pin "2") (pinfunction "2_2") (pintype "passive"))
      (node (ref "C128") (pin "2") (pinfunction "2_2") (pintype "passive"))
      (node (ref "C129") (pin "2") (pinfunction "2_2") (pintype "passive"))
      (node (ref "C130") (pin "2") (pinfunction "2_2") (pintype "passive"))
      (node (ref "C131") (pin "2") (pinfunction "2_2") (pintype "passive"))
      (node (ref "C132") (pin "1") (pinfunction "1_1") (pintype "passive"))
      (node (ref "C133") (pin "1") (pinfunction "1_1") (pintype "passive"))
      (node (ref "C134") (pin "2") (pinfunction "2_2") (pintype "passive"))
      (node (ref "C135") (pin "1") (pinfunction "1_1") (pintype "passive"))
      (node (ref "C136") (pin "1") (pinfunction "1_1") (pintype "passive"))
      (node (ref "C137") (pin "2") (pinfunction "2_2") (pintype "passive"))
      (node (ref "C138") (pin "2") (pinfunction "2_2") (pintype "passive"))
      (node (ref "C139") (pin "1") (pinfunction "1_1") (pintype "passive"))
      (node (ref "R124") (pin "2") (pinfunction "2_2") (pintype "passive"))
      (node (ref "R131") (pin "1") (pinfunction "1_1") (pintype "passive"))
      (node (ref "R132") (pin "1") (pinfunction "1_1") (pintype "passive"))
      (node (ref "R133") (pin "1") (pinfunction "1_1") (pintype "passive"))
      (node (ref "R134") (pin "1") (pinfunction "1_1") (pintype "passive"))
      (node (ref "R135") (pin "1") (pinfunction "1_1") (pintype "passive"))
      (node (ref "R136") (pin "1") (pinfunction "1_1") (pintype "passive"))
      (node (ref "R143") (pin "2") (pinfunction "2_2") (pintype "passive"))
      (node (ref "R144") (pin "2") (pinfunction "2_2") (pintype "passive"))
      (node (ref "R148") (pin "2") (pinfunction "2_2") (pintype "passive"))
      (node (ref "R155") (pin "1") (pinfunction "1_1") (pintype "passive"))
      (node (ref "R156") (pin "1") (pinfunction "1_1") (pintype "passive"))
      (node (ref "R157") (pin "1") (pinfunction "1_1") (pintype "passive"))
      (node (ref "R158") (pin "1") (pinfunction "1_1") (pintype "passive"))
      (node (ref "R159") (pin "1") (pinfunction "1_1") (pintype "passive"))
      (node (ref "U18") (pin "1") (pinfunction "NC_1") (pintype "passive"))
      (node (ref "U18") (pin "2") (pinfunction "NC_2") (pintype "passive"))
      (node (ref "U18") (pin "3") (pinfunction "NC_3") (pintype "passive"))
      (node (ref "U18") (pin "4") (pinfunction "VSS_4") (pintype "power_in"))
      (node (ref "U18") (pin "7") (pinfunction "WP_7") (pintype "input"))
      (node (ref "U19") (pin "33") (pinfunction "PAD_33") (pintype "power_in"))
      (node (ref "U20") (pin "2") (pinfunction "GND_2") (pintype "power_in"))
      (node (ref "U21") (pin "33") (pinfunction "PAD_33") (pintype "power_in"))
    )
    (net (code "49") (name "Net-(D7-A)") (class "Default")
      (node (ref "D7") (pin "2") (pinfunction "A_2") (pintype "passive"))
      (node (ref "R141") (pin "1") (pinfunction "1_1") (pintype "passive"))
    )
    (net (code "50") (name "Net-(D7-K)") (class "Default")
      (node (ref "D7") (pin "1") (pinfunction "K_1") (pintype "passive"))
      (node (ref "U20") (pin "6") (pinfunction "1Y_6") (pintype "open_collector"))
    )
    (net (code "51") (name "Net-(D8-A)") (class "Default")
      (node (ref "D8") (pin "2") (pinfunction "A_2") (pintype "passive"))
      (node (ref "R142") (pin "2") (pinfunction "2_2") (pintype "passive"))
    )
    (net (code "52") (name "Net-(D8-K)") (class "Default")
      (node (ref "D8") (pin "1") (pinfunction "K_1") (pintype "passive"))
      (node (ref "U20") (pin "4") (pinfunction "2Y_4") (pintype "open_collector"))
    )
    (net (code "53") (name "Net-(J5-CHS_GND)") (class "Default")
      (node (ref "C121") (pin "2") (pinfunction "2_2") (pintype "passive"))
      (node (ref "J5") (pin "10") (pinfunction "CHS_GND_10") (pintype "power_in"))
      (node (ref "J5") (pin "13") (pinfunction "Shield_13") (pintype "passive"))
      (node (ref "J5") (pin "14") (pinfunction "Shield_14") (pintype "passive"))
    )
    (net (code "54") (name "Net-(J5-LEFT_LED_ANODE)") (class "Default")
      (node (ref "J5") (pin "12") (pinfunction "LEFT_LED_ANODE_12") (pintype "passive"))
      (node (ref "R129") (pin "2") (pinfunction "2_2") (pintype "passive"))
    )
    (net (code "55") (name "Net-(J5-RIGHT_LED_ANODE)") (class "Default")
      (node (ref "J5") (pin "1") (pinfunction "RIGHT_LED_ANODE_1") (pintype "passive"))
      (node (ref "R138") (pin "2") (pinfunction "2_2") (pintype "passive"))
    )
    (net (code "56") (name "Net-(J6-CHS_GND)") (class "Default")
      (node (ref "C139") (pin "2") (pinfunction "2_2") (pintype "passive"))
      (node (ref "J6") (pin "10") (pinfunction "CHS_GND_10") (pintype "power_in"))
      (node (ref "J6") (pin "13") (pinfunction "Shield_13") (pintype "passive"))
      (node (ref "J6") (pin "14") (pinfunction "Shield_14") (pintype "passive"))
    )
    (net (code "57") (name "Net-(J6-LEFT_LED_ANODE)") (class "Default")
      (node (ref "J6") (pin "12") (pinfunction "LEFT_LED_ANODE_12") (pintype "passive"))
      (node (ref "R153") (pin "2") (pinfunction "2_2") (pintype "passive"))
    )
    (net (code "58") (name "Net-(J6-RIGHT_LED_ANODE)") (class "Default")
      (node (ref "J6") (pin "1") (pinfunction "RIGHT_LED_ANODE_1") (pintype "passive"))
      (node (ref "R161") (pin "2") (pinfunction "2_2") (pintype "passive"))
    )
    (net (code "59") (name "Net-(U19-COL{slash}GPIO2)") (class "Default")
      (node (ref "R136") (pin "2") (pinfunction "2_2") (pintype "passive"))
      (node (ref "U19") (pin "29") (pinfunction "COL/GPIO2_29") (pintype "bidirectional"))
    )
    (net (code "60") (name "Net-(U19-CRS{slash}CRS_DV)") (class "Default")
      (node (ref "R123") (pin "1") (pinfunction "1_1") (pintype "passive"))
      (node (ref "U19") (pin "27") (pinfunction "CRS/CRS_DV_27") (pintype "output"))
    )
    (net (code "61") (name "Net-(U19-INT{slash}PWDN)") (class "Default")
      (node (ref "R128") (pin "1") (pinfunction "1_1") (pintype "passive"))
      (node (ref "U19") (pin "8") (pinfunction "INT/PWDN_8") (pintype "bidirectional"))
    )
    (net (code "62") (name "Net-(U19-LED_1{slash}GPIO1)") (class "Default")
      (node (ref "R130") (pin "2") (pinfunction "2_2") (pintype "passive"))
      (node (ref "U19") (pin "24") (pinfunction "LED_1/GPIO1_24") (pintype "bidirectional"))
    )
    (net (code "63") (name "Net-(U19-RBIAS)") (class "Default")
      (node (ref "R124") (pin "1") (pinfunction "1_1") (pintype "passive"))
      (node (ref "U19") (pin "16") (pinfunction "RBIAS_16") (pintype "passive"))
    )
    (net (code "64") (name "Net-(U21-COL{slash}GPIO2)") (class "Default")
      (node (ref "R146") (pin "1") (pinfunction "1_1") (pintype "passive"))
      (node (ref "U21") (pin "29") (pinfunction "COL/GPIO2_29") (pintype "bidirectional"))
    )
    (net (code "65") (name "Net-(U21-CRS{slash}CRS_DV)") (class "Default")
      (node (ref "R145") (pin "1") (pinfunction "1_1") (pintype "passive"))
      (node (ref "U21") (pin "27") (pinfunction "CRS/CRS_DV_27") (pintype "output"))
    )
    (net (code "66") (name "Net-(U21-INT{slash}PWDN)") (class "Default")
      (node (ref "R151") (pin "1") (pinfunction "1_1") (pintype "passive"))
      (node (ref "U21") (pin "8") (pinfunction "INT/PWDN_8") (pintype "bidirectional"))
    )
    (net (code "67") (name "Net-(U21-LED_1{slash}GPIO1)") (class "Default")
      (node (ref "R154") (pin "2") (pinfunction "2_2") (pintype "passive"))
      (node (ref "U21") (pin "24") (pinfunction "LED_1/GPIO1_24") (pintype "bidirectional"))
    )
    (net (code "68") (name "Net-(U21-RBIAS)") (class "Default")
      (node (ref "R148") (pin "1") (pinfunction "1_1") (pintype "passive"))
      (node (ref "U21") (pin "16") (pinfunction "RBIAS_16") (pintype "passive"))
    )
    (net (code "69") (name "VDD_3V3") (class "Default")
      (node (ref "C104") (pin "1") (pinfunction "1_1") (pintype "passive"))
      (node (ref "C105") (pin "1") (pinfunction "1_1") (pintype "passive"))
      (node (ref "C106") (pin "1") (pinfunction "1_1") (pintype "passive"))
      (node (ref "C107") (pin "1") (pinfunction "1_1") (pintype "passive"))
      (node (ref "C108") (pin "1") (pinfunction "1_1") (pintype "passive"))
      (node (ref "C109") (pin "1") (pinfunction "1_1") (pintype "passive"))
      (node (ref "C110") (pin "1") (pinfunction "1_1") (pintype "passive"))
      (node (ref "C111") (pin "1") (pinfunction "1_1") (pintype "passive"))
      (node (ref "C112") (pin "1") (pinfunction "1_1") (pintype "passive"))
      (node (ref "C113") (pin "1") (pinfunction "1_1") (pintype "passive"))
      (node (ref "C114") (pin "2") (pinfunction "2_2") (pintype "passive"))
      (node (ref "C115") (pin "1") (pinfunction "1_1") (pintype "passive"))
      (node (ref "C116") (pin "2") (pinfunction "2_2") (pintype "passive"))
      (node (ref "C117") (pin "2") (pinfunction "2_2") (pintype "passive"))
      (node (ref "C118") (pin "2") (pinfunction "2_2") (pintype "passive"))
      (node (ref "C119") (pin "1") (pinfunction "1_1") (pintype "passive"))
      (node (ref "C120") (pin "1") (pinfunction "1_1") (pintype "passive"))
      (node (ref "C122") (pin "1") (pinfunction "1_1") (pintype "passive"))
      (node (ref "C123") (pin "1") (pinfunction "1_1") (pintype "passive"))
      (node (ref "C124") (pin "1") (pinfunction "1_1") (pintype "passive"))
      (node (ref "C125") (pin "1") (pinfunction "1_1") (pintype "passive"))
      (node (ref "C126") (pin "1") (pinfunction "1_1") (pintype "passive"))
      (node (ref "C127") (pin "1") (pinfunction "1_1") (pintype "passive"))
      (node (ref "C128") (pin "1") (pinfunction "1_1") (pintype "passive"))
      (node (ref "C129") (pin "1") (pinfunction "1_1") (pintype "passive"))
      (node (ref "C130") (pin "1") (pinfunction "1_1") (pintype "passive"))
      (node (ref "C131") (pin "1") (pinfunction "1_1") (pintype "passive"))
      (node (ref "C132") (pin "2") (pinfunction "2_2") (pintype "passive"))
      (node (ref "C133") (pin "2") (pinfunction "2_2") (pintype "passive"))
      (node (ref "C134") (pin "1") (pinfunction "1_1") (pintype "passive"))
      (node (ref "C135") (pin "2") (pinfunction "2_2") (pintype "passive"))
      (node (ref "C136") (pin "2") (pinfunction "2_2") (pintype "passive"))
      (node (ref "C137") (pin "1") (pinfunction "1_1") (pintype "passive"))
      (node (ref "C138") (pin "1") (pinfunction "1_1") (pintype "passive"))
      (node (ref "J5") (pin "5") (pinfunction "TCT_5") (pintype "passive"))
      (node (ref "J5") (pin "6") (pinfunction "RCT_6") (pintype "passive"))
      (node (ref "J6") (pin "5") (pinfunction "TCT_5") (pintype "passive"))
      (node (ref "J6") (pin "6") (pinfunction "RCT_6") (pintype "passive"))
      (node (ref "R118") (pin "2") (pinfunction "2_2") (pintype "passive"))
      (node (ref "R119") (pin "2") (pinfunction "2_2") (pintype "passive"))
      (node (ref "R120") (pin "2") (pinfunction "2_2") (pintype "passive"))
      (node (ref "R121") (pin "2") (pinfunction "2_2") (pintype "passive"))
      (node (ref "R122") (pin "2") (pinfunction "2_2") (pintype "passive"))
      (node (ref "R123") (pin "2") (pinfunction "2_2") (pintype "passive"))
      (node (ref "R125") (pin "2") (pinfunction "2_2") (pintype "passive"))
      (node (ref "R126") (pin "2") (pinfunction "2_2") (pintype "passive"))
      (node (ref "R127") (pin "1") (pinfunction "1_1") (pintype "passive"))
      (node (ref "R128") (pin "2") (pinfunction "2_2") (pintype "passive"))
      (node (ref "R129") (pin "1") (pinfunction "1_1") (pintype "passive"))
      (node (ref "R130") (pin "1") (pinfunction "1_1") (pintype "passive"))
      (node (ref "R137") (pin "2") (pinfunction "2_2") (pintype "passive"))
      (node (ref "R138") (pin "1") (pinfunction "1_1") (pintype "passive"))
      (node (ref "R139") (pin "2") (pinfunction "2_2") (pintype "passive"))
      (node (ref "R140") (pin "2") (pinfunction "2_2") (pintype "passive"))
      (node (ref "R141") (pin "2") (pinfunction "2_2") (pintype "passive"))
      (node (ref "R142") (pin "1") (pinfunction "1_1") (pintype "passive"))
      (node (ref "R145") (pin "2") (pinfunction "2_2") (pintype "passive"))
      (node (ref "R146") (pin "2") (pinfunction "2_2") (pintype "passive"))
      (node (ref "R147") (pin "2") (pinfunction "2_2") (pintype "passive"))
      (node (ref "R149") (pin "2") (pinfunction "2_2") (pintype "passive"))
      (node (ref "R150") (pin "2") (pinfunction "2_2") (pintype "passive"))
      (node (ref "R151") (pin "2") (pinfunction "2_2") (pintype "passive"))
      (node (ref "R152") (pin "1") (pinfunction "1_1") (pintype "passive"))
      (node (ref "R153") (pin "1") (pinfunction "1_1") (pintype "passive"))
      (node (ref "R154") (pin "1") (pinfunction "1_1") (pintype "passive"))
      (node (ref "R160") (pin "2") (pinfunction "2_2") (pintype "passive"))
      (node (ref "R161") (pin "1") (pinfunction "1_1") (pintype "passive"))
      (node (ref "U18") (pin "8") (pinfunction "VCC_8") (pintype "power_in"))
      (node (ref "U19") (pin "14") (pinfunction "AVD_14") (pintype "power_in"))
      (node (ref "U19") (pin "21") (pinfunction "VDDIO_21") (pintype "power_in"))
      (node (ref "U20") (pin "5") (pinfunction "VCC_5") (pintype "power_in"))
      (node (ref "U21") (pin "14") (pinfunction "AVD_14") (pintype "power_in"))
      (node (ref "U21") (pin "21") (pinfunction "VDDIO_21") (pintype "power_in"))
    )
    (net (code "70") (name "unconnected-(J5-NC-Pad9)") (class "Default")
      (node (ref "J5") (pin "9") (pinfunction "NC_9") (pintype "passive+no_connect"))
    )
    (net (code "71") (name "unconnected-(J6-NC-Pad9)") (class "Default")
      (node (ref "J6") (pin "9") (pinfunction "NC_9") (pintype "passive+no_connect"))
    )
    (net (code "72") (name "unconnected-(U19-NC-Pad13)") (class "Default")
      (node (ref "U19") (pin "13") (pinfunction "NC_13") (pintype "passive+no_connect"))
    )
    (net (code "73") (name "unconnected-(U19-NC-Pad15)") (class "Default")
      (node (ref "U19") (pin "15") (pinfunction "NC_15") (pintype "passive+no_connect"))
    )
    (net (code "74") (name "unconnected-(U19-XO-Pad22)") (class "Default")
      (node (ref "U19") (pin "22") (pinfunction "XO_22") (pintype "passive+no_connect"))
    )
    (net (code "75") (name "unconnected-(U21-NC-Pad13)") (class "Default")
      (node (ref "U21") (pin "13") (pinfunction "NC_13") (pintype "passive+no_connect"))
    )
    (net (code "76") (name "unconnected-(U21-NC-Pad15)") (class "Default")
      (node (ref "U21") (pin "15") (pinfunction "NC_15") (pintype "passive+no_connect"))
    )
    (net (code "77") (name "unconnected-(U21-XO-Pad22)") (class "Default")
      (node (ref "U21") (pin "22") (pinfunction "XO_22") (pintype "passive+no_connect"))
    )
  )
)
